# design.net
KiCad netlist of a schematic drawn in Altium Designer
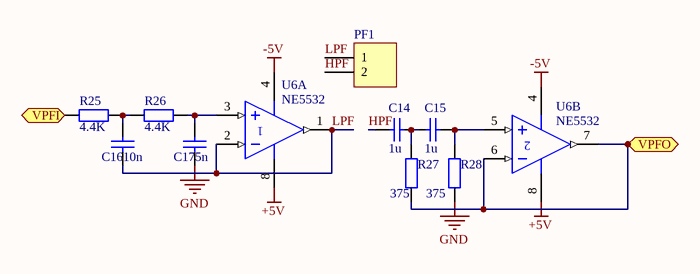
[diagram p0: 音频滤波.SchDoc]

(export (version "E")
  (design (tool "Eeschema 10.0.6"))
  (components
    (comp (ref "C14")
      (value "瓷片电容")
      (footprint "瓷片电容")
      (fields (field (name "ALTIUM_UNNAMED_1") "1u"))
      (libsource (lib "自制库（原理图文件）") (part "瓷片电容"))
    )
    (comp (ref "C15")
      (value "瓷片电容")
      (footprint "瓷片电容")
      (fields (field (name "ALTIUM_UNNAMED_1") "1u"))
      (libsource (lib "自制库（原理图文件）") (part "瓷片电容"))
    )
    (comp (ref "C16")
      (value "瓷片电容")
      (footprint "瓷片电容")
      (fields (field (name "ALTIUM_UNNAMED_1") "10n"))
      (libsource (lib "自制库（原理图文件）") (part "瓷片电容"))
    )
    (comp (ref "C17")
      (value "瓷片电容")
      (footprint "瓷片电容")
      (fields (field (name "ALTIUM_UNNAMED_1") "5n"))
      (libsource (lib "自制库（原理图文件）") (part "瓷片电容"))
    )
    (comp (ref "PF1")
      (value "Header 2")
      (footprint "HDR1X2")
      (description "Header, 2-Pin")
      (fields (field (name "PUBLISHER") "Altium Limited"))
      (libsource (lib "Miscellaneous Connectors") (part "Header 2"))
    )
    (comp (ref "R25")
      (value "4.4K")
      (footprint "AXIAL-0.4")
      (description "Resistor")
      (fields (field (name "Comment") "Res2") (field (name "PUBLISHER") "Altium Limited"))
      (libsource (lib "") (part "Res2_1"))
    )
    (comp (ref "R26")
      (value "4.4K")
      (footprint "AXIAL-0.4")
      (description "Resistor")
      (fields (field (name "Comment") "Res2") (field (name "PUBLISHER") "Altium Limited"))
      (libsource (lib "") (part "Res2_1"))
    )
    (comp (ref "R27")
      (value "375")
      (footprint "AXIAL-0.4")
      (description "Resistor")
      (fields (field (name "Comment") "Res2") (field (name "PUBLISHER") "Altium Limited"))
      (libsource (lib "Miscellaneous Devices") (part "Res2"))
    )
    (comp (ref "R28")
      (value "375")
      (footprint "AXIAL-0.4")
      (description "Resistor")
      (fields (field (name "Comment") "Res2") (field (name "PUBLISHER") "Altium Limited"))
      (libsource (lib "Miscellaneous Devices") (part "Res2"))
    )
    (comp (ref "U6")
      (value "NE5532")
      (footprint "JG008")
      (description "Dual Low-Noise Operational Amplifier")
      (fields (field (name "PUBLISHER") "Altium Limited"))
      (libsource (lib "TI Operational Amplifier") (part "NE5532AJG"))
    )
  )
  (nets
    (net (code "1") (name "+5V") (class "Default")
      (node (ref "U6") (pin "8") (pinfunction "V+_8") (pintype "power_in"))
    )
    (net (code "2") (name "-5V") (class "Default")
      (node (ref "U6") (pin "4") (pinfunction "V-_4") (pintype "power_in"))
    )
    (net (code "3") (name "/HPF") (class "Default")
      (node (ref "C14") (pin "2") (pinfunction "2_2") (pintype "passive"))
      (node (ref "PF1") (pin "2") (pinfunction "2_2") (pintype "passive"))
    )
    (net (code "4") (name "/LPF") (class "Default")
      (node (ref "C16") (pin "1") (pinfunction "1_1") (pintype "passive"))
      (node (ref "PF1") (pin "1") (pinfunction "1_1") (pintype "passive"))
      (node (ref "U6") (pin "1") (pinfunction "OUT_1") (pintype "output"))
      (node (ref "U6") (pin "2") (pinfunction "IN-_2") (pintype "input"))
    )
    (net (code "5") (name "/VPFI") (class "Default")
      (node (ref "R25") (pin "2") (pinfunction "2_2") (pintype "passive"))
    )
    (net (code "6") (name "/VPFO") (class "Default")
      (node (ref "R27") (pin "1") (pinfunction "1_1") (pintype "passive"))
      (node (ref "U6") (pin "6") (pinfunction "IN-_6") (pintype "input"))
      (node (ref "U6") (pin "7") (pinfunction "OUT_7") (pintype "output"))
    )
    (net (code "7") (name "GND") (class "Default")
      (node (ref "C17") (pin "1") (pinfunction "1_1") (pintype "passive"))
      (node (ref "R28") (pin "1") (pinfunction "1_1") (pintype "passive"))
    )
    (net (code "8") (name "Net-(C14-Pad1)") (class "Default")
      (node (ref "C14") (pin "1") (pinfunction "1_1") (pintype "passive"))
      (node (ref "C15") (pin "2") (pinfunction "2_2") (pintype "passive"))
      (node (ref "R27") (pin "2") (pinfunction "2_2") (pintype "passive"))
    )
    (net (code "9") (name "Net-(C16-Pad2)") (class "Default")
      (node (ref "C16") (pin "2") (pinfunction "2_2") (pintype "passive"))
      (node (ref "R25") (pin "1") (pinfunction "1_1") (pintype "passive"))
      (node (ref "R26") (pin "2") (pinfunction "2_2") (pintype "passive"))
    )
    (net (code "10") (name "Net-(U6A-IN+)") (class "Default")
      (node (ref "C17") (pin "2") (pinfunction "2_2") (pintype "passive"))
      (node (ref "R26") (pin "1") (pinfunction "1_1") (pintype "passive"))
      (node (ref "U6") (pin "3") (pinfunction "IN+_3") (pintype "input"))
    )
    (net (code "11") (name "Net-(U6B-IN+)") (class "Default")
      (node (ref "C15") (pin "1") (pinfunction "1_1") (pintype "passive"))
      (node (ref "R28") (pin "2") (pinfunction "2_2") (pintype "passive"))
      (node (ref "U6") (pin "5") (pinfunction "IN+_5") (pintype "input"))
    )
  )
)
